# Pressure.net
KiCad netlist of a schematic drawn in Altium Designer
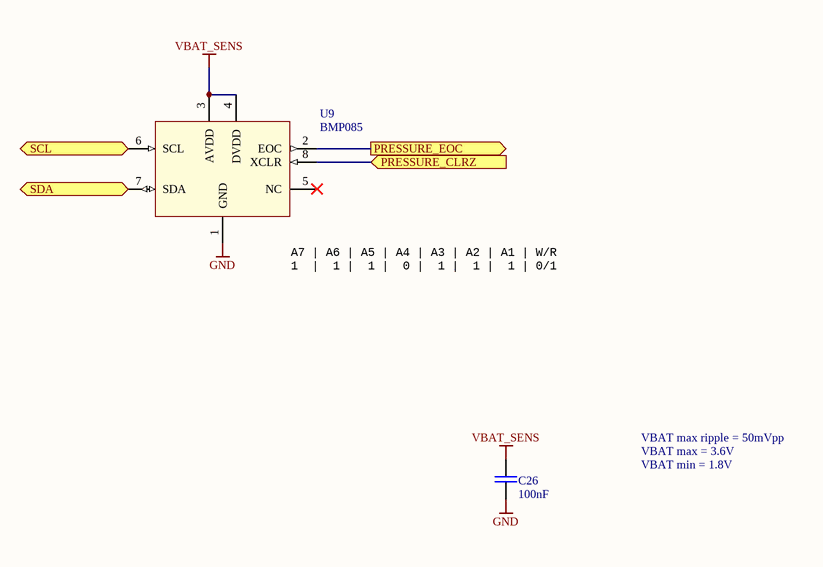
[diagram p0: Pressure.SchDoc]

(export (version "E")
  (design (tool "Eeschema 10.0.6"))
  (components
    (comp (ref "C26")
      (value "100nF")
      (footprint "0603")
      (description "Capacitor")
      (fields (field (name "OWNER") "Nuno Brum"))
      (libsource (lib "Alcetronics_Devices") (part "CAP"))
    )
    (comp (ref "U9")
      (value "BMP085")
      (footprint "CLCC-8")
      (description "Digital Pressure Sensor")
      (libsource (lib "Alcetronics_IC") (part "BMP085"))
    )
  )
  (nets
    (net (code "1") (name "/PRESSURE_CLRZ") (class "Default")
      (node (ref "U9") (pin "8") (pinfunction "XCLR_8") (pintype "input"))
    )
    (net (code "2") (name "/PRESSURE_EOC") (class "Default")
      (node (ref "U9") (pin "2") (pinfunction "EOC_2") (pintype "output"))
    )
    (net (code "3") (name "/SCL") (class "Default")
      (node (ref "U9") (pin "6") (pinfunction "SCL_6") (pintype "input"))
    )
    (net (code "4") (name "/SDA") (class "Default")
      (node (ref "U9") (pin "7") (pinfunction "SDA_7") (pintype "bidirectional"))
    )
    (net (code "5") (name "GND") (class "Default")
      (node (ref "C26") (pin "1") (pinfunction "1_1") (pintype "passive"))
      (node (ref "U9") (pin "1") (pinfunction "GND_1") (pintype "power_in"))
    )
    (net (code "6") (name "VBAT_SENS") (class "Default")
      (node (ref "C26") (pin "2") (pinfunction "2_2") (pintype "passive"))
      (node (ref "U9") (pin "3") (pinfunction "AVDD_3") (pintype "power_in"))
      (node (ref "U9") (pin "4") (pinfunction "DVDD_4") (pintype "power_in"))
    )
    (net (code "7") (name "unconnected-(U9-NC-Pad5)") (class "Default")
      (node (ref "U9") (pin "5") (pinfunction "NC_5") (pintype "passive+no_connect"))
    )
  )
)
